# design.net
KiCad netlist of a schematic drawn in Altium Designer
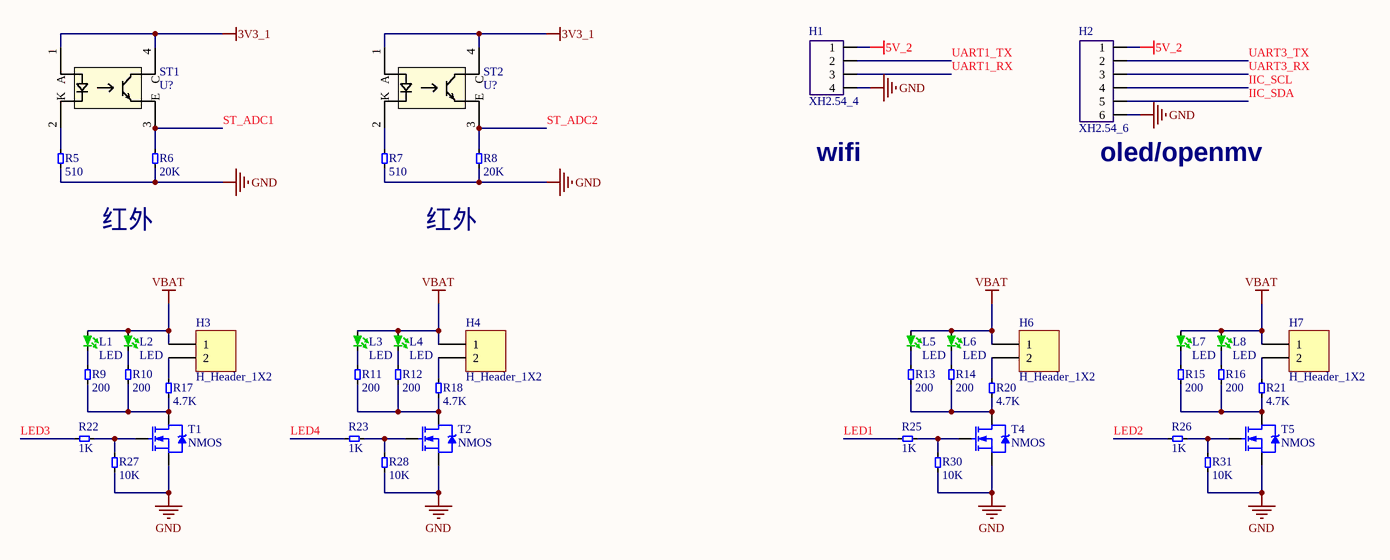
[diagram p0: 其他.SchDoc]

(export (version "E")
  (design (tool "Eeschema 10.0.6"))
  (components
    (comp (ref "H1")
      (value "XH2.54_4")
      (footprint "H_XH2.54_4")
      (description "4脚小白头")
      (fields (field (name "PUBLISHER") "Altium Limited"))
      (libsource (lib "接插件") (part "H_XH2.54_4"))
    )
    (comp (ref "H2")
      (value "XH2.54_6")
      (footprint "H_XH2.54_6")
      (description "6脚小白头")
      (fields (field (name "PUBLISHER") "Altium Limited"))
      (libsource (lib "接插件") (part "H_XH2.54_6"))
    )
    (comp (ref "H3")
      (value "H_Header_1X2")
      (footprint "H_Header_1X2")
      (description "单排2针排针")
      (fields (field (name "PUBLISHER") "Altium Limited"))
      (libsource (lib "接插件") (part "H_Header_1X2"))
    )
    (comp (ref "H4")
      (value "H_Header_1X2")
      (footprint "H_Header_1X2")
      (description "单排2针排针")
      (fields (field (name "PUBLISHER") "Altium Limited"))
      (libsource (lib "接插件") (part "H_Header_1X2"))
    )
    (comp (ref "H6")
      (value "H_Header_1X2")
      (footprint "H_Header_1X2")
      (description "单排2针排针")
      (fields (field (name "PUBLISHER") "Altium Limited"))
      (libsource (lib "接插件") (part "H_Header_1X2"))
    )
    (comp (ref "H7")
      (value "H_Header_1X2")
      (footprint "H_Header_1X2")
      (description "单排2针排针")
      (fields (field (name "PUBLISHER") "Altium Limited"))
      (libsource (lib "接插件") (part "H_Header_1X2"))
    )
    (comp (ref "L1")
      (value "LED")
      (footprint "C_1206")
      (description "绿色LED")
      (libsource (lib "声光元件") (part "Y_LED_G"))
    )
    (comp (ref "L2")
      (value "LED")
      (footprint "C_1206")
      (description "绿色LED")
      (libsource (lib "声光元件") (part "Y_LED_G"))
    )
    (comp (ref "L3")
      (value "LED")
      (footprint "C_1206")
      (description "绿色LED")
      (libsource (lib "声光元件") (part "Y_LED_G"))
    )
    (comp (ref "L4")
      (value "LED")
      (footprint "C_1206")
      (description "绿色LED")
      (libsource (lib "声光元件") (part "Y_LED_G"))
    )
    (comp (ref "L5")
      (value "LED")
      (footprint "C_1206")
      (description "绿色LED")
      (libsource (lib "声光元件") (part "Y_LED_G"))
    )
    (comp (ref "L6")
      (value "LED")
      (footprint "C_1206")
      (description "绿色LED")
      (libsource (lib "声光元件") (part "Y_LED_G"))
    )
    (comp (ref "L7")
      (value "LED")
      (footprint "C_1206")
      (description "绿色LED")
      (libsource (lib "声光元件") (part "Y_LED_G"))
    )
    (comp (ref "L8")
      (value "LED")
      (footprint "C_1206")
      (description "绿色LED")
      (libsource (lib "声光元件") (part "Y_LED_G"))
    )
    (comp (ref "R5")
      (value "510")
      (footprint "R_0603")
      (description "贴片电阻")
      (libsource (lib "电阻电容电感库") (part "R_贴片"))
    )
    (comp (ref "R6")
      (value "20K")
      (footprint "R_0603")
      (description "贴片电阻")
      (libsource (lib "电阻电容电感库") (part "R_贴片"))
    )
    (comp (ref "R7")
      (value "510")
      (footprint "R_0603")
      (description "贴片电阻")
      (libsource (lib "电阻电容电感库") (part "R_贴片"))
    )
    (comp (ref "R8")
      (value "20K")
      (footprint "R_0603")
      (description "贴片电阻")
      (libsource (lib "电阻电容电感库") (part "R_贴片"))
    )
    (comp (ref "R9")
      (value "200")
      (footprint "R_0603")
      (description "贴片电阻")
      (libsource (lib "电阻电容电感库") (part "R_贴片"))
    )
    (comp (ref "R10")
      (value "200")
      (footprint "R_0603")
      (description "贴片电阻")
      (libsource (lib "电阻电容电感库") (part "R_贴片"))
    )
    (comp (ref "R11")
      (value "200")
      (footprint "R_0603")
      (description "贴片电阻")
      (libsource (lib "电阻电容电感库") (part "R_贴片"))
    )
    (comp (ref "R12")
      (value "200")
      (footprint "R_0603")
      (description "贴片电阻")
      (libsource (lib "电阻电容电感库") (part "R_贴片"))
    )
    (comp (ref "R13")
      (value "200")
      (footprint "R_0603")
      (description "贴片电阻")
      (libsource (lib "电阻电容电感库") (part "R_贴片"))
    )
    (comp (ref "R14")
      (value "200")
      (footprint "R_0603")
      (description "贴片电阻")
      (libsource (lib "电阻电容电感库") (part "R_贴片"))
    )
    (comp (ref "R15")
      (value "200")
      (footprint "R_0603")
      (description "贴片电阻")
      (libsource (lib "电阻电容电感库") (part "R_贴片"))
    )
    (comp (ref "R16")
      (value "200")
      (footprint "R_0603")
      (description "贴片电阻")
      (libsource (lib "电阻电容电感库") (part "R_贴片"))
    )
    (comp (ref "R17")
      (value "4.7K")
      (footprint "R_0603")
      (description "贴片电阻")
      (libsource (lib "电阻电容电感库") (part "R_贴片"))
    )
    (comp (ref "R18")
      (value "4.7K")
      (footprint "R_0603")
      (description "贴片电阻")
      (libsource (lib "电阻电容电感库") (part "R_贴片"))
    )
    (comp (ref "R20")
      (value "4.7K")
      (footprint "R_0603")
      (description "贴片电阻")
      (libsource (lib "电阻电容电感库") (part "R_贴片"))
    )
    (comp (ref "R21")
      (value "4.7K")
      (footprint "R_0603")
      (description "贴片电阻")
      (libsource (lib "电阻电容电感库") (part "R_贴片"))
    )
    (comp (ref "R22")
      (value "1K")
      (footprint "R_0603")
      (description "贴片电阻")
      (libsource (lib "电阻电容电感库") (part "R_贴片"))
    )
    (comp (ref "R23")
      (value "1K")
      (footprint "R_0603")
      (description "贴片电阻")
      (libsource (lib "电阻电容电感库") (part "R_贴片"))
    )
    (comp (ref "R25")
      (value "1K")
      (footprint "R_0603")
      (description "贴片电阻")
      (libsource (lib "电阻电容电感库") (part "R_贴片"))
    )
    (comp (ref "R26")
      (value "1K")
      (footprint "R_0603")
      (description "贴片电阻")
      (libsource (lib "电阻电容电感库") (part "R_贴片"))
    )
    (comp (ref "R27")
      (value "10K")
      (footprint "R_0603")
      (description "贴片电阻")
      (libsource (lib "电阻电容电感库") (part "R_贴片"))
    )
    (comp (ref "R28")
      (value "10K")
      (footprint "R_0603")
      (description "贴片电阻")
      (libsource (lib "电阻电容电感库") (part "R_贴片"))
    )
    (comp (ref "R30")
      (value "10K")
      (footprint "R_0603")
      (description "贴片电阻")
      (libsource (lib "电阻电容电感库") (part "R_贴片"))
    )
    (comp (ref "R31")
      (value "10K")
      (footprint "R_0603")
      (description "贴片电阻")
      (libsource (lib "电阻电容电感库") (part "R_贴片"))
    )
    (comp (ref "ST1") (value "U?") (footprint "ST188") (libsource (lib "王建勇") (part "ST188")))
    (comp (ref "ST2") (value "U?") (footprint "ST188") (libsource (lib "王建勇") (part "ST188")))
    (comp (ref "T1")
      (value "NMOS")
      (footprint "T_MOS_SOT-23")
      (description "N沟道MOS管")
      (fields (field (name "PUBLISHER") "Altium Limited"))
      (libsource (lib "晶体管") (part "T_MOSFET_N"))
    )
    (comp (ref "T2")
      (value "NMOS")
      (footprint "T_MOS_SOT-23")
      (description "N沟道MOS管")
      (fields (field (name "PUBLISHER") "Altium Limited"))
      (libsource (lib "晶体管") (part "T_MOSFET_N"))
    )
    (comp (ref "T4")
      (value "NMOS")
      (footprint "T_MOS_SOT-23")
      (description "N沟道MOS管")
      (fields (field (name "PUBLISHER") "Altium Limited"))
      (libsource (lib "晶体管") (part "T_MOSFET_N"))
    )
    (comp (ref "T5")
      (value "NMOS")
      (footprint "T_MOS_SOT-23")
      (description "N沟道MOS管")
      (fields (field (name "PUBLISHER") "Altium Limited"))
      (libsource (lib "晶体管") (part "T_MOSFET_N"))
    )
  )
  (nets
    (net (code "1") (name "/IIC_SCL") (class "Default")
      (node (ref "H2") (pin "4") (pinfunction "4_4") (pintype "passive"))
    )
    (net (code "2") (name "/IIC_SDA") (class "Default")
      (node (ref "H2") (pin "5") (pinfunction "5_5") (pintype "passive"))
    )
    (net (code "3") (name "/LED1") (class "Default") (node (ref "R25") (pin "2") (pintype "passive")))
    (net (code "4") (name "/LED2") (class "Default") (node (ref "R26") (pin "2") (pintype "passive")))
    (net (code "5") (name "/LED3") (class "Default") (node (ref "R22") (pin "2") (pintype "passive")))
    (net (code "6") (name "/LED4") (class "Default") (node (ref "R23") (pin "2") (pintype "passive")))
    (net (code "7") (name "/ST_ADC1") (class "Default")
      (node (ref "R6") (pin "2") (pintype "passive"))
      (node (ref "ST1") (pin "3") (pinfunction "E_3") (pintype "passive"))
    )
    (net (code "8") (name "/ST_ADC2") (class "Default")
      (node (ref "R8") (pin "2") (pintype "passive"))
      (node (ref "ST2") (pin "3") (pinfunction "E_3") (pintype "passive"))
    )
    (net (code "9") (name "/UART1_RX") (class "Default")
      (node (ref "H1") (pin "3") (pinfunction "3_3") (pintype "passive"))
    )
    (net (code "10") (name "/UART1_TX") (class "Default")
      (node (ref "H1") (pin "2") (pinfunction "2_2") (pintype "passive"))
    )
    (net (code "11") (name "/UART3_RX") (class "Default")
      (node (ref "H2") (pin "3") (pinfunction "3_3") (pintype "passive"))
    )
    (net (code "12") (name "/UART3_TX") (class "Default")
      (node (ref "H2") (pin "2") (pinfunction "2_2") (pintype "passive"))
    )
    (net (code "13") (name "3V3_1") (class "Default")
      (node (ref "ST1") (pin "1") (pinfunction "A_1") (pintype "passive"))
      (node (ref "ST1") (pin "4") (pinfunction "C_4") (pintype "passive"))
      (node (ref "ST2") (pin "1") (pinfunction "A_1") (pintype "passive"))
      (node (ref "ST2") (pin "4") (pinfunction "C_4") (pintype "passive"))
    )
    (net (code "14") (name "5V_2") (class "Default")
      (node (ref "H1") (pin "1") (pinfunction "1_1") (pintype "passive"))
      (node (ref "H2") (pin "1") (pinfunction "1_1") (pintype "passive"))
    )
    (net (code "15") (name "GND") (class "Default")
      (node (ref "H1") (pin "4") (pinfunction "4_4") (pintype "passive"))
      (node (ref "H2") (pin "6") (pinfunction "6_6") (pintype "passive"))
      (node (ref "R27") (pin "1") (pintype "passive"))
      (node (ref "R28") (pin "1") (pintype "passive"))
      (node (ref "R30") (pin "1") (pintype "passive"))
      (node (ref "R31") (pin "1") (pintype "passive"))
      (node (ref "R5") (pin "1") (pintype "passive"))
      (node (ref "R6") (pin "1") (pintype "passive"))
      (node (ref "R7") (pin "1") (pintype "passive"))
      (node (ref "R8") (pin "1") (pintype "passive"))
      (node (ref "T1") (pin "2") (pinfunction "S_2") (pintype "passive"))
      (node (ref "T2") (pin "2") (pinfunction "S_2") (pintype "passive"))
      (node (ref "T4") (pin "2") (pinfunction "S_2") (pintype "passive"))
      (node (ref "T5") (pin "2") (pinfunction "S_2") (pintype "passive"))
    )
    (net (code "16") (name "Net-(H3-Pad2)") (class "Default")
      (node (ref "H3") (pin "2") (pinfunction "2_2") (pintype "passive"))
      (node (ref "R17") (pin "2") (pintype "passive"))
    )
    (net (code "17") (name "Net-(H4-Pad2)") (class "Default")
      (node (ref "H4") (pin "2") (pinfunction "2_2") (pintype "passive"))
      (node (ref "R18") (pin "2") (pintype "passive"))
    )
    (net (code "18") (name "Net-(H6-Pad2)") (class "Default")
      (node (ref "H6") (pin "2") (pinfunction "2_2") (pintype "passive"))
      (node (ref "R20") (pin "2") (pintype "passive"))
    )
    (net (code "19") (name "Net-(H7-Pad2)") (class "Default")
      (node (ref "H7") (pin "2") (pinfunction "2_2") (pintype "passive"))
      (node (ref "R21") (pin "2") (pintype "passive"))
    )
    (net (code "20") (name "Net-(L1-Pad2)") (class "Default")
      (node (ref "L1") (pin "2") (pintype "passive"))
      (node (ref "R9") (pin "2") (pintype "passive"))
    )
    (net (code "21") (name "Net-(L2-Pad2)") (class "Default")
      (node (ref "L2") (pin "2") (pintype "passive"))
      (node (ref "R10") (pin "2") (pintype "passive"))
    )
    (net (code "22") (name "Net-(L3-Pad2)") (class "Default")
      (node (ref "L3") (pin "2") (pintype "passive"))
      (node (ref "R11") (pin "2") (pintype "passive"))
    )
    (net (code "23") (name "Net-(L4-Pad2)") (class "Default")
      (node (ref "L4") (pin "2") (pintype "passive"))
      (node (ref "R12") (pin "2") (pintype "passive"))
    )
    (net (code "24") (name "Net-(L5-Pad2)") (class "Default")
      (node (ref "L5") (pin "2") (pintype "passive"))
      (node (ref "R13") (pin "2") (pintype "passive"))
    )
    (net (code "25") (name "Net-(L6-Pad2)") (class "Default")
      (node (ref "L6") (pin "2") (pintype "passive"))
      (node (ref "R14") (pin "2") (pintype "passive"))
    )
    (net (code "26") (name "Net-(L7-Pad2)") (class "Default")
      (node (ref "L7") (pin "2") (pintype "passive"))
      (node (ref "R15") (pin "2") (pintype "passive"))
    )
    (net (code "27") (name "Net-(L8-Pad2)") (class "Default")
      (node (ref "L8") (pin "2") (pintype "passive"))
      (node (ref "R16") (pin "2") (pintype "passive"))
    )
    (net (code "28") (name "Net-(ST1-K)") (class "Default")
      (node (ref "R5") (pin "2") (pintype "passive"))
      (node (ref "ST1") (pin "2") (pinfunction "K_2") (pintype "passive"))
    )
    (net (code "29") (name "Net-(ST2-K)") (class "Default")
      (node (ref "R7") (pin "2") (pintype "passive"))
      (node (ref "ST2") (pin "2") (pinfunction "K_2") (pintype "passive"))
    )
    (net (code "30") (name "Net-(T1-D)") (class "Default")
      (node (ref "R10") (pin "1") (pintype "passive"))
      (node (ref "R17") (pin "1") (pintype "passive"))
      (node (ref "R9") (pin "1") (pintype "passive"))
      (node (ref "T1") (pin "3") (pinfunction "D_3") (pintype "passive"))
    )
    (net (code "31") (name "Net-(T1-G)") (class "Default")
      (node (ref "R22") (pin "1") (pintype "passive"))
      (node (ref "R27") (pin "2") (pintype "passive"))
      (node (ref "T1") (pin "1") (pinfunction "G_1") (pintype "passive"))
    )
    (net (code "32") (name "Net-(T2-D)") (class "Default")
      (node (ref "R11") (pin "1") (pintype "passive"))
      (node (ref "R12") (pin "1") (pintype "passive"))
      (node (ref "R18") (pin "1") (pintype "passive"))
      (node (ref "T2") (pin "3") (pinfunction "D_3") (pintype "passive"))
    )
    (net (code "33") (name "Net-(T2-G)") (class "Default")
      (node (ref "R23") (pin "1") (pintype "passive"))
      (node (ref "R28") (pin "2") (pintype "passive"))
      (node (ref "T2") (pin "1") (pinfunction "G_1") (pintype "passive"))
    )
    (net (code "34") (name "Net-(T4-D)") (class "Default")
      (node (ref "R13") (pin "1") (pintype "passive"))
      (node (ref "R14") (pin "1") (pintype "passive"))
      (node (ref "R20") (pin "1") (pintype "passive"))
      (node (ref "T4") (pin "3") (pinfunction "D_3") (pintype "passive"))
    )
    (net (code "35") (name "Net-(T4-G)") (class "Default")
      (node (ref "R25") (pin "1") (pintype "passive"))
      (node (ref "R30") (pin "2") (pintype "passive"))
      (node (ref "T4") (pin "1") (pinfunction "G_1") (pintype "passive"))
    )
    (net (code "36") (name "Net-(T5-D)") (class "Default")
      (node (ref "R15") (pin "1") (pintype "passive"))
      (node (ref "R16") (pin "1") (pintype "passive"))
      (node (ref "R21") (pin "1") (pintype "passive"))
      (node (ref "T5") (pin "3") (pinfunction "D_3") (pintype "passive"))
    )
    (net (code "37") (name "Net-(T5-G)") (class "Default")
      (node (ref "R26") (pin "1") (pintype "passive"))
      (node (ref "R31") (pin "2") (pintype "passive"))
      (node (ref "T5") (pin "1") (pinfunction "G_1") (pintype "passive"))
    )
    (net (code "38") (name "VBAT") (class "Default")
      (node (ref "H3") (pin "1") (pinfunction "1_1") (pintype "passive"))
      (node (ref "H4") (pin "1") (pinfunction "1_1") (pintype "passive"))
      (node (ref "H6") (pin "1") (pinfunction "1_1") (pintype "passive"))
      (node (ref "H7") (pin "1") (pinfunction "1_1") (pintype "passive"))
      (node (ref "L1") (pin "1") (pintype "passive"))
      (node (ref "L2") (pin "1") (pintype "passive"))
      (node (ref "L3") (pin "1") (pintype "passive"))
      (node (ref "L4") (pin "1") (pintype "passive"))
      (node (ref "L5") (pin "1") (pintype "passive"))
      (node (ref "L6") (pin "1") (pintype "passive"))
      (node (ref "L7") (pin "1") (pintype "passive"))
      (node (ref "L8") (pin "1") (pintype "passive"))
    )
  )
)
